# eagleSchem.net
KiCad netlist of a schematic drawn in EAGLE
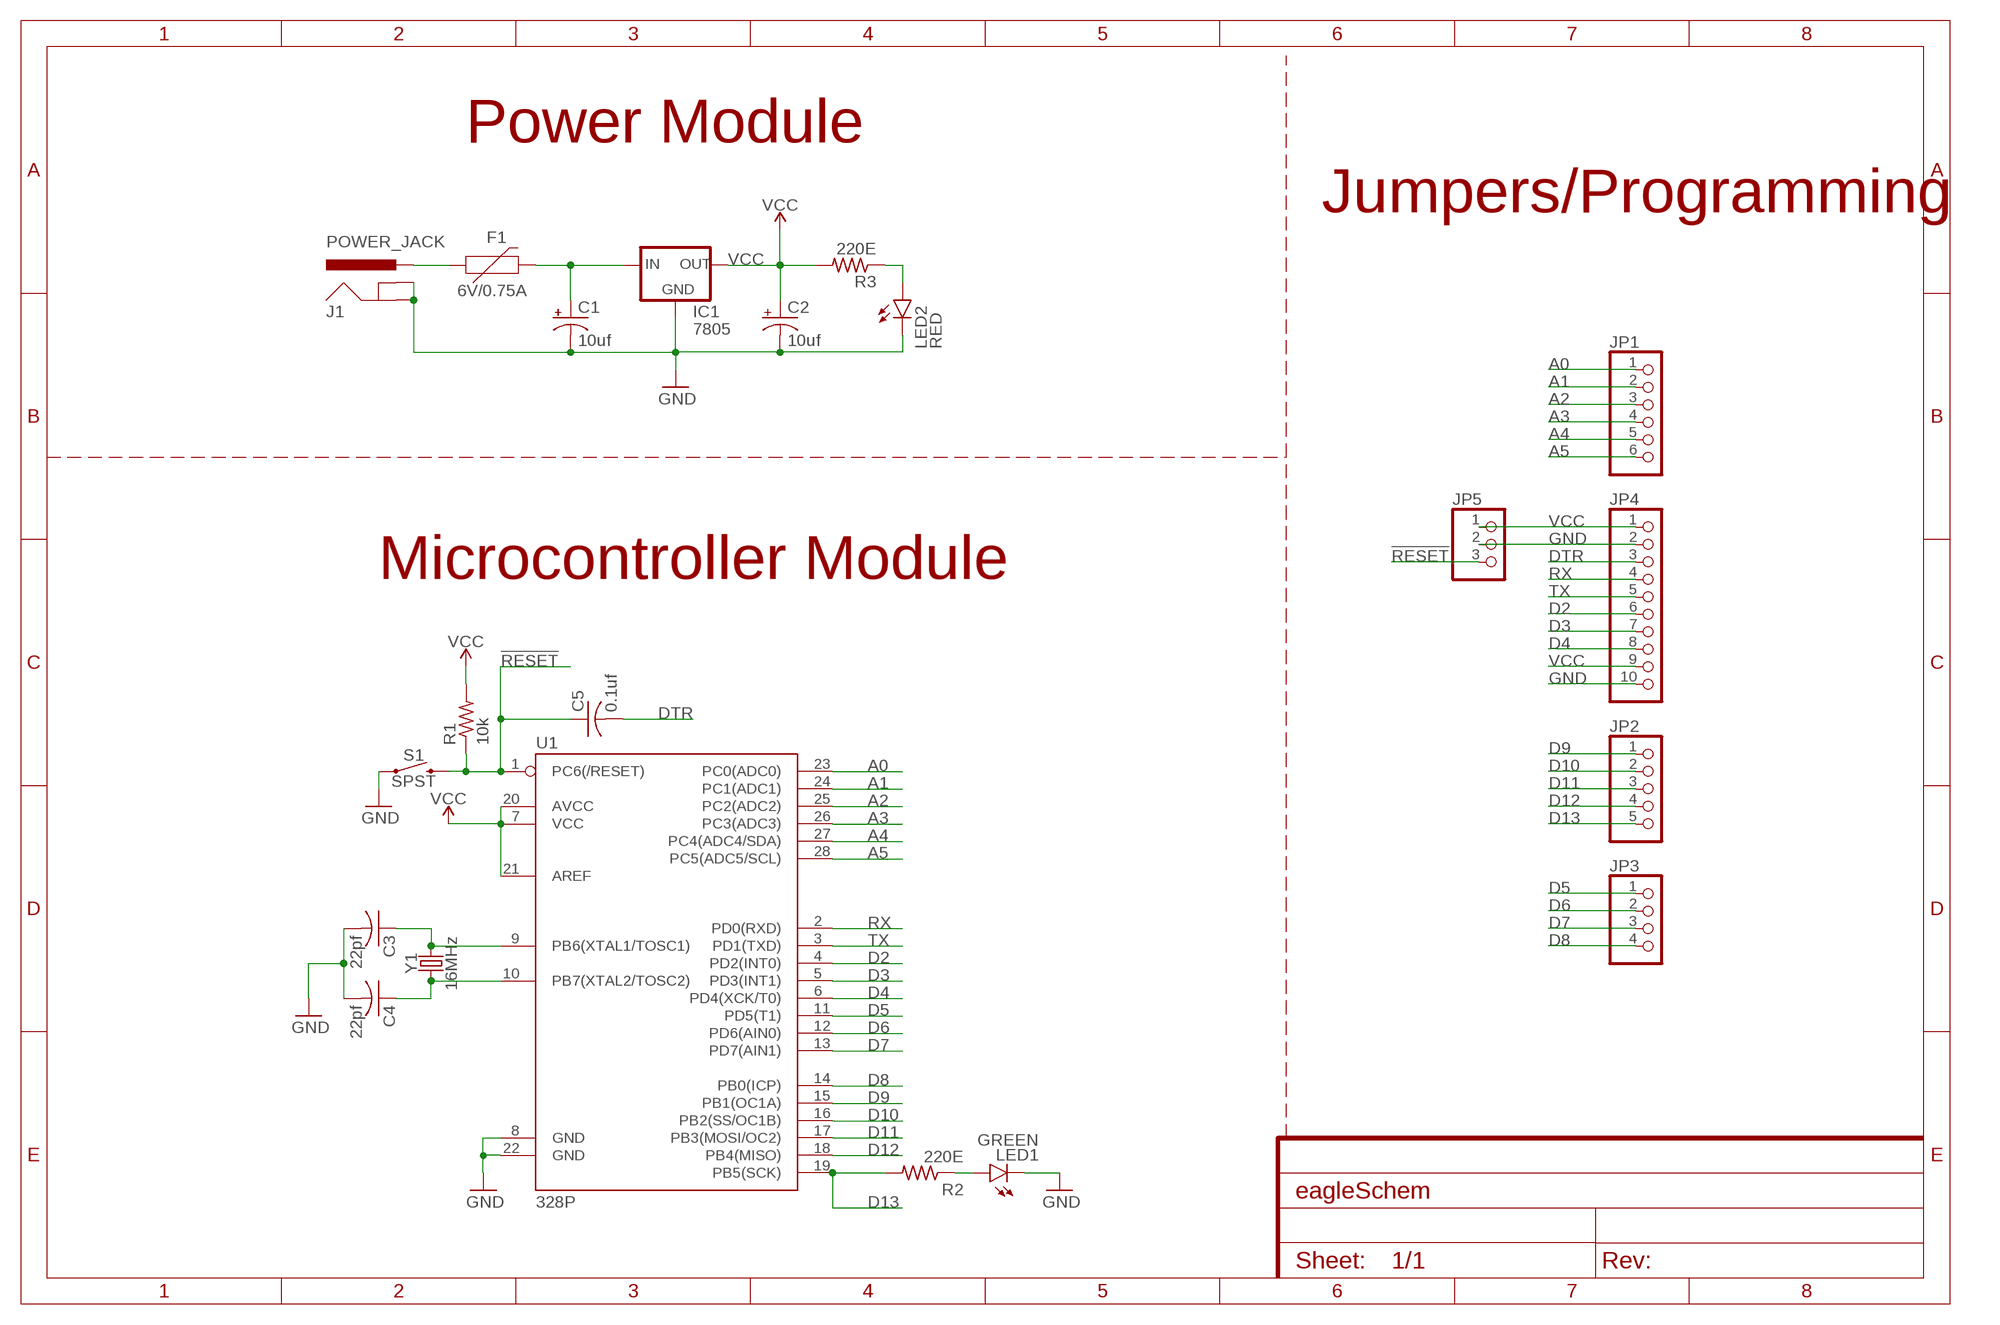
[diagram p0: schematic, sheet 1]

(export (version "E")
  (design (tool "Eeschema 10.0.6"))
  (components
    (comp (ref "C1")
      (value "10uf")
      (footprint "eagle-import:E2,5-6")
      (libsource (lib "eagle-import") (part "CPOL-USE2.5-6"))
    )
    (comp (ref "C2")
      (value "10uf")
      (footprint "eagle-import:E2,5-6")
      (libsource (lib "eagle-import") (part "CPOL-USE2.5-6"))
    )
    (comp (ref "C3")
      (value "22pf")
      (footprint "eagle-import:C025-024X044")
      (libsource (lib "eagle-import") (part "C-US025-024X044"))
    )
    (comp (ref "C4")
      (value "22pf")
      (footprint "eagle-import:C025-024X044")
      (libsource (lib "eagle-import") (part "C-US025-024X044"))
    )
    (comp (ref "C5")
      (value "0.1uf")
      (footprint "eagle-import:C025-024X044")
      (libsource (lib "eagle-import") (part "C-US025-024X044"))
    )
    (comp (ref "F1")
      (value "6V/0.75A")
      (footprint "eagle-import:1206")
      (libsource (lib "eagle-import") (part "PPTC_0.75A"))
    )
    (comp (ref "IC1")
      (value "7805")
      (footprint "eagle-import:78XXS")
      (libsource (lib "eagle-import") (part "78XXS"))
    )
    (comp (ref "J1")
      (value "POWER_JACK")
      (footprint "eagle-import:POWER_JACK_PTH")
      (libsource (lib "eagle-import") (part "POWER_JACK"))
    )
    (comp (ref "JP1")
      (value "PINHD-1X6")
      (footprint "eagle-import:1X06")
      (libsource (lib "eagle-import") (part "PINHD-1X6"))
    )
    (comp (ref "JP2")
      (value "PINHD-1X5")
      (footprint "eagle-import:1X05")
      (libsource (lib "eagle-import") (part "PINHD-1X5"))
    )
    (comp (ref "JP3")
      (value "PINHD-1X4")
      (footprint "eagle-import:1X04")
      (libsource (lib "eagle-import") (part "PINHD-1X4"))
    )
    (comp (ref "JP4")
      (value "PINHD-1X10")
      (footprint "eagle-import:1X10")
      (libsource (lib "eagle-import") (part "PINHD-1X10"))
    )
    (comp (ref "JP5")
      (value "PINHD-1X3")
      (footprint "eagle-import:1X03")
      (libsource (lib "eagle-import") (part "PINHD-1X3"))
    )
    (comp (ref "LED1")
      (value "GREEN")
      (footprint "eagle-import:LED3MM")
      (libsource (lib "eagle-import") (part "LED3MM"))
    )
    (comp (ref "LED2")
      (value "RED")
      (footprint "eagle-import:LED3MM")
      (libsource (lib "eagle-import") (part "LED3MM"))
    )
    (comp (ref "R1")
      (value "10k")
      (footprint "eagle-import:0204_7")
      (libsource (lib "eagle-import") (part "R-US_0204/7"))
    )
    (comp (ref "R2")
      (value "220E")
      (footprint "eagle-import:0204_7")
      (libsource (lib "eagle-import") (part "R-US_0204/7"))
    )
    (comp (ref "R3")
      (value "220E")
      (footprint "eagle-import:0204_7")
      (libsource (lib "eagle-import") (part "R-US_0204/7"))
    )
    (comp (ref "S1")
      (value "SPST")
      (footprint "eagle-import:TACTILE_SWITCH_PTH_6.0MM")
      (libsource (lib "eagle-import") (part "MOMENTARY-SWITCH-SPST-PTH-6.0MM"))
    )
    (comp (ref "U1")
      (value "328P")
      (footprint "eagle-import:DIP28")
      (libsource (lib "eagle-import") (part "ATMEGA328P_PDIP"))
    )
    (comp (ref "Y1")
      (value "16MHz")
      (footprint "eagle-import:HC49US")
      (libsource (lib "eagle-import") (part "CRYSTAL-16MHZPTH-HC49US"))
    )
  )
  (nets
    (net (code "1") (name "/A0") (class "Default")
      (node (ref "JP1") (pin "1") (pinfunction "1_1") (pintype "passive"))
      (node (ref "U1") (pin "23") (pinfunction "PC0(ADC0)_23") (pintype "bidirectional"))
    )
    (net (code "2") (name "/A1") (class "Default")
      (node (ref "JP1") (pin "2") (pinfunction "2_2") (pintype "passive"))
      (node (ref "U1") (pin "24") (pinfunction "PC1(ADC1)_24") (pintype "bidirectional"))
    )
    (net (code "3") (name "/A2") (class "Default")
      (node (ref "JP1") (pin "3") (pinfunction "3_3") (pintype "passive"))
      (node (ref "U1") (pin "25") (pinfunction "PC2(ADC2)_25") (pintype "bidirectional"))
    )
    (net (code "4") (name "/A3") (class "Default")
      (node (ref "JP1") (pin "4") (pinfunction "4_4") (pintype "passive"))
      (node (ref "U1") (pin "26") (pinfunction "PC3(ADC3)_26") (pintype "bidirectional"))
    )
    (net (code "5") (name "/A4") (class "Default")
      (node (ref "JP1") (pin "5") (pinfunction "5_5") (pintype "passive"))
      (node (ref "U1") (pin "27") (pinfunction "PC4(ADC4/SDA)_27") (pintype "bidirectional"))
    )
    (net (code "6") (name "/A5") (class "Default")
      (node (ref "JP1") (pin "6") (pinfunction "6_6") (pintype "passive"))
      (node (ref "U1") (pin "28") (pinfunction "PC5(ADC5/SCL)_28") (pintype "bidirectional"))
    )
    (net (code "7") (name "/D2") (class "Default")
      (node (ref "JP4") (pin "6") (pinfunction "6_6") (pintype "passive"))
      (node (ref "U1") (pin "4") (pinfunction "PD2(INT0)_4") (pintype "bidirectional"))
    )
    (net (code "8") (name "/D3") (class "Default")
      (node (ref "JP4") (pin "7") (pinfunction "7_7") (pintype "passive"))
      (node (ref "U1") (pin "5") (pinfunction "PD3(INT1)_5") (pintype "bidirectional"))
    )
    (net (code "9") (name "/D4") (class "Default")
      (node (ref "JP4") (pin "8") (pinfunction "8_8") (pintype "passive"))
      (node (ref "U1") (pin "6") (pinfunction "PD4(XCK/T0)_6") (pintype "bidirectional"))
    )
    (net (code "10") (name "/D5") (class "Default")
      (node (ref "JP3") (pin "1") (pinfunction "1_1") (pintype "passive"))
      (node (ref "U1") (pin "11") (pinfunction "PD5(T1)_11") (pintype "bidirectional"))
    )
    (net (code "11") (name "/D6") (class "Default")
      (node (ref "JP3") (pin "2") (pinfunction "2_2") (pintype "passive"))
      (node (ref "U1") (pin "12") (pinfunction "PD6(AIN0)_12") (pintype "bidirectional"))
    )
    (net (code "12") (name "/D7") (class "Default")
      (node (ref "JP3") (pin "3") (pinfunction "3_3") (pintype "passive"))
      (node (ref "U1") (pin "13") (pinfunction "PD7(AIN1)_13") (pintype "bidirectional"))
    )
    (net (code "13") (name "/D8") (class "Default")
      (node (ref "JP3") (pin "4") (pinfunction "4_4") (pintype "passive"))
      (node (ref "U1") (pin "14") (pinfunction "PB0(ICP)_14") (pintype "bidirectional"))
    )
    (net (code "14") (name "/D9") (class "Default")
      (node (ref "JP2") (pin "1") (pinfunction "1_1") (pintype "passive"))
      (node (ref "U1") (pin "15") (pinfunction "PB1(OC1A)_15") (pintype "bidirectional"))
    )
    (net (code "15") (name "/D10") (class "Default")
      (node (ref "JP2") (pin "2") (pinfunction "2_2") (pintype "passive"))
      (node (ref "U1") (pin "16") (pinfunction "PB2(SS/OC1B)_16") (pintype "bidirectional"))
    )
    (net (code "16") (name "/D11") (class "Default")
      (node (ref "JP2") (pin "3") (pinfunction "3_3") (pintype "passive"))
      (node (ref "U1") (pin "17") (pinfunction "PB3(MOSI/OC2)_17") (pintype "bidirectional"))
    )
    (net (code "17") (name "/D12") (class "Default")
      (node (ref "JP2") (pin "4") (pinfunction "4_4") (pintype "passive"))
      (node (ref "U1") (pin "18") (pinfunction "PB4(MISO)_18") (pintype "bidirectional"))
    )
    (net (code "18") (name "/D13") (class "Default")
      (node (ref "JP2") (pin "5") (pinfunction "5_5") (pintype "passive"))
      (node (ref "R2") (pin "2") (pinfunction "2_2") (pintype "passive"))
      (node (ref "U1") (pin "19") (pinfunction "PB5(SCK)_19") (pintype "bidirectional"))
    )
    (net (code "19") (name "/DTR") (class "Default")
      (node (ref "C5") (pin "2") (pinfunction "2_2") (pintype "passive"))
      (node (ref "JP4") (pin "3") (pinfunction "3_3") (pintype "passive"))
    )
    (net (code "20") (name "/RX") (class "Default")
      (node (ref "JP4") (pin "4") (pinfunction "4_4") (pintype "passive"))
      (node (ref "U1") (pin "2") (pinfunction "PD0(RXD)_2") (pintype "bidirectional"))
    )
    (net (code "21") (name "/TX") (class "Default")
      (node (ref "JP4") (pin "5") (pinfunction "5_5") (pintype "passive"))
      (node (ref "U1") (pin "3") (pinfunction "PD1(TXD)_3") (pintype "bidirectional"))
    )
    (net (code "22") (name "/~{RESET}") (class "Default")
      (node (ref "C5") (pin "1") (pinfunction "1_1") (pintype "passive"))
      (node (ref "JP5") (pin "3") (pinfunction "3_3") (pintype "passive"))
      (node (ref "R1") (pin "1") (pinfunction "1_1") (pintype "passive"))
      (node (ref "S1") (pin "3") (pinfunction "2_3") (pintype "passive"))
      (node (ref "U1") (pin "1") (pinfunction "PC6(/RESET)_1") (pintype "bidirectional"))
    )
    (net (code "23") (name "GND") (class "Default")
      (node (ref "C1") (pin "-") (pinfunction "-_-") (pintype "passive"))
      (node (ref "C2") (pin "-") (pinfunction "-_-") (pintype "passive"))
      (node (ref "C3") (pin "2") (pinfunction "2_2") (pintype "passive"))
      (node (ref "C4") (pin "2") (pinfunction "2_2") (pintype "passive"))
      (node (ref "IC1") (pin "GND") (pinfunction "GND_GND") (pintype "input"))
      (node (ref "J1") (pin "GND") (pinfunction "GND_GND") (pintype "bidirectional"))
      (node (ref "J1") (pin "GNDBREAK") (pinfunction "GNDBREAK_GNDBREAK") (pintype "bidirectional"))
      (node (ref "JP4") (pin "10") (pinfunction "10_10") (pintype "passive"))
      (node (ref "JP4") (pin "2") (pinfunction "2_2") (pintype "passive"))
      (node (ref "JP5") (pin "2") (pinfunction "2_2") (pintype "passive"))
      (node (ref "LED1") (pin "K") (pinfunction "C_K") (pintype "passive"))
      (node (ref "LED2") (pin "K") (pinfunction "C_K") (pintype "passive"))
      (node (ref "S1") (pin "1") (pinfunction "1_1") (pintype "passive"))
      (node (ref "U1") (pin "22") (pinfunction "GND_22") (pintype "bidirectional"))
      (node (ref "U1") (pin "8") (pinfunction "GND_8") (pintype "bidirectional"))
    )
    (net (code "24") (name "Net-(C1-Pad+)") (class "Default")
      (node (ref "C1") (pin "+") (pinfunction "+_+") (pintype "passive"))
      (node (ref "F1") (pin "2") (pinfunction "2_2") (pintype "bidirectional"))
      (node (ref "IC1") (pin "IN") (pinfunction "IN_IN") (pintype "input"))
    )
    (net (code "25") (name "Net-(F1-Pad1)") (class "Default")
      (node (ref "F1") (pin "1") (pinfunction "1_1") (pintype "bidirectional"))
      (node (ref "J1") (pin "PWR") (pinfunction "PWR_PWR") (pintype "bidirectional"))
    )
    (net (code "26") (name "Net-(LED1-PadA)") (class "Default")
      (node (ref "LED1") (pin "A") (pinfunction "A_A") (pintype "passive"))
      (node (ref "R2") (pin "1") (pinfunction "1_1") (pintype "passive"))
    )
    (net (code "27") (name "Net-(LED2-PadA)") (class "Default")
      (node (ref "LED2") (pin "A") (pinfunction "A_A") (pintype "passive"))
      (node (ref "R3") (pin "1") (pinfunction "1_1") (pintype "passive"))
    )
    (net (code "28") (name "Net-(U1-PB6(XTAL1{slash}TOSC1))") (class "Default")
      (node (ref "C3") (pin "1") (pinfunction "1_1") (pintype "passive"))
      (node (ref "U1") (pin "9") (pinfunction "PB6(XTAL1/TOSC1)_9") (pintype "bidirectional"))
      (node (ref "Y1") (pin "2") (pinfunction "2_2") (pintype "passive"))
    )
    (net (code "29") (name "Net-(U1-PB7(XTAL2{slash}TOSC2))") (class "Default")
      (node (ref "C4") (pin "1") (pinfunction "1_1") (pintype "passive"))
      (node (ref "U1") (pin "10") (pinfunction "PB7(XTAL2/TOSC2)_10") (pintype "bidirectional"))
      (node (ref "Y1") (pin "1") (pinfunction "1_1") (pintype "passive"))
    )
    (net (code "30") (name "VCC") (class "Default")
      (node (ref "C2") (pin "+") (pinfunction "+_+") (pintype "passive"))
      (node (ref "IC1") (pin "OUT") (pinfunction "OUT_OUT") (pintype "passive"))
      (node (ref "JP4") (pin "1") (pinfunction "1_1") (pintype "passive"))
      (node (ref "JP4") (pin "9") (pinfunction "9_9") (pintype "passive"))
      (node (ref "JP5") (pin "1") (pinfunction "1_1") (pintype "passive"))
      (node (ref "R1") (pin "2") (pinfunction "2_2") (pintype "passive"))
      (node (ref "R3") (pin "2") (pinfunction "2_2") (pintype "passive"))
      (node (ref "U1") (pin "20") (pinfunction "AVCC_20") (pintype "bidirectional"))
      (node (ref "U1") (pin "21") (pinfunction "AREF_21") (pintype "bidirectional"))
      (node (ref "U1") (pin "7") (pinfunction "VCC_7") (pintype "bidirectional"))
    )
  )
)
